# MicroController.net
KiCad netlist of a schematic drawn in Altium Designer
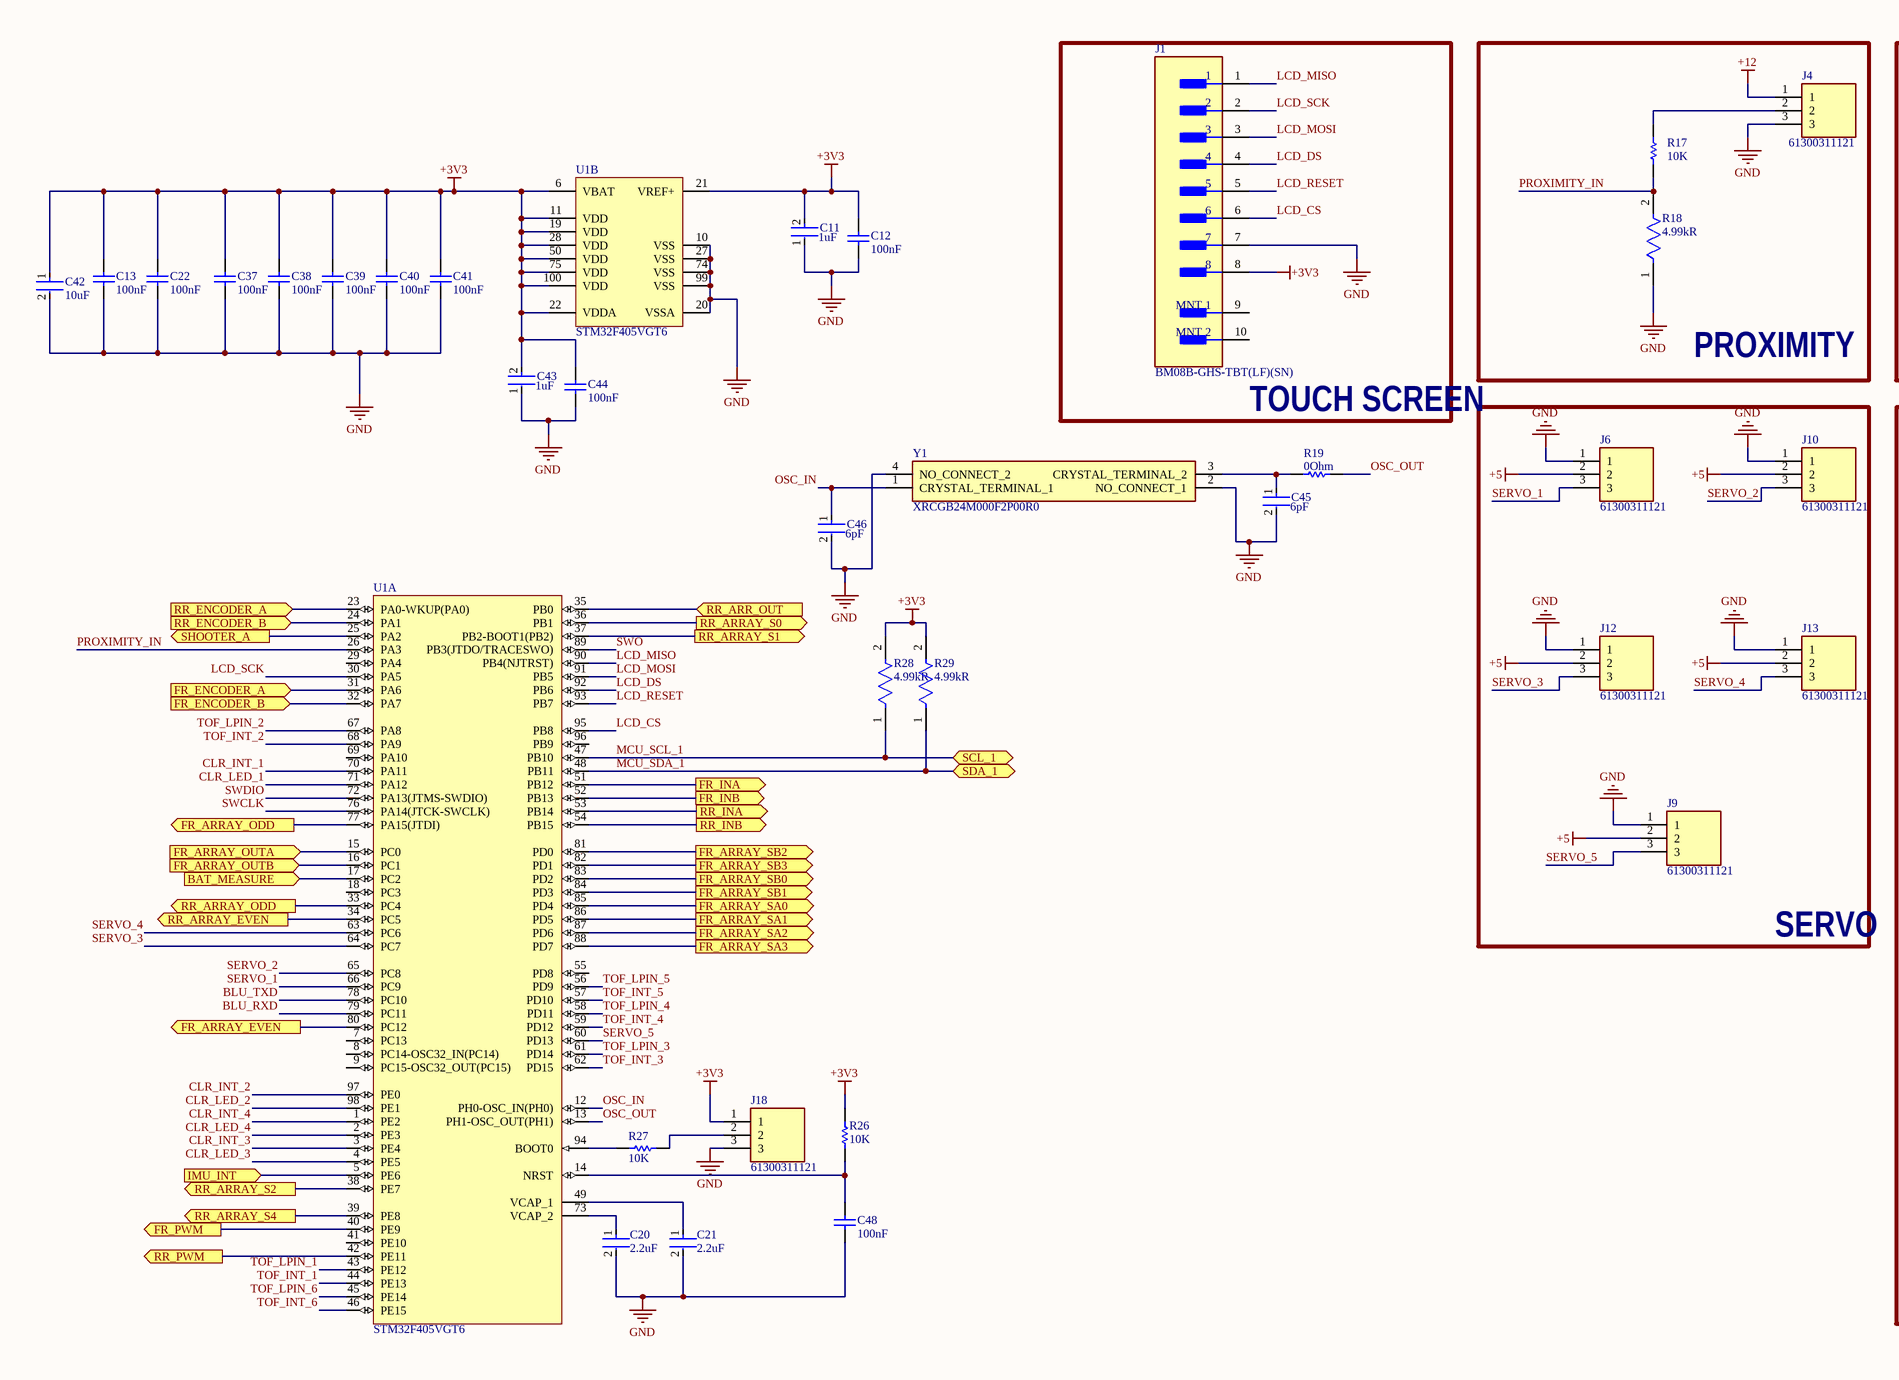
[diagram p0: MicroController.SchDoc, left]
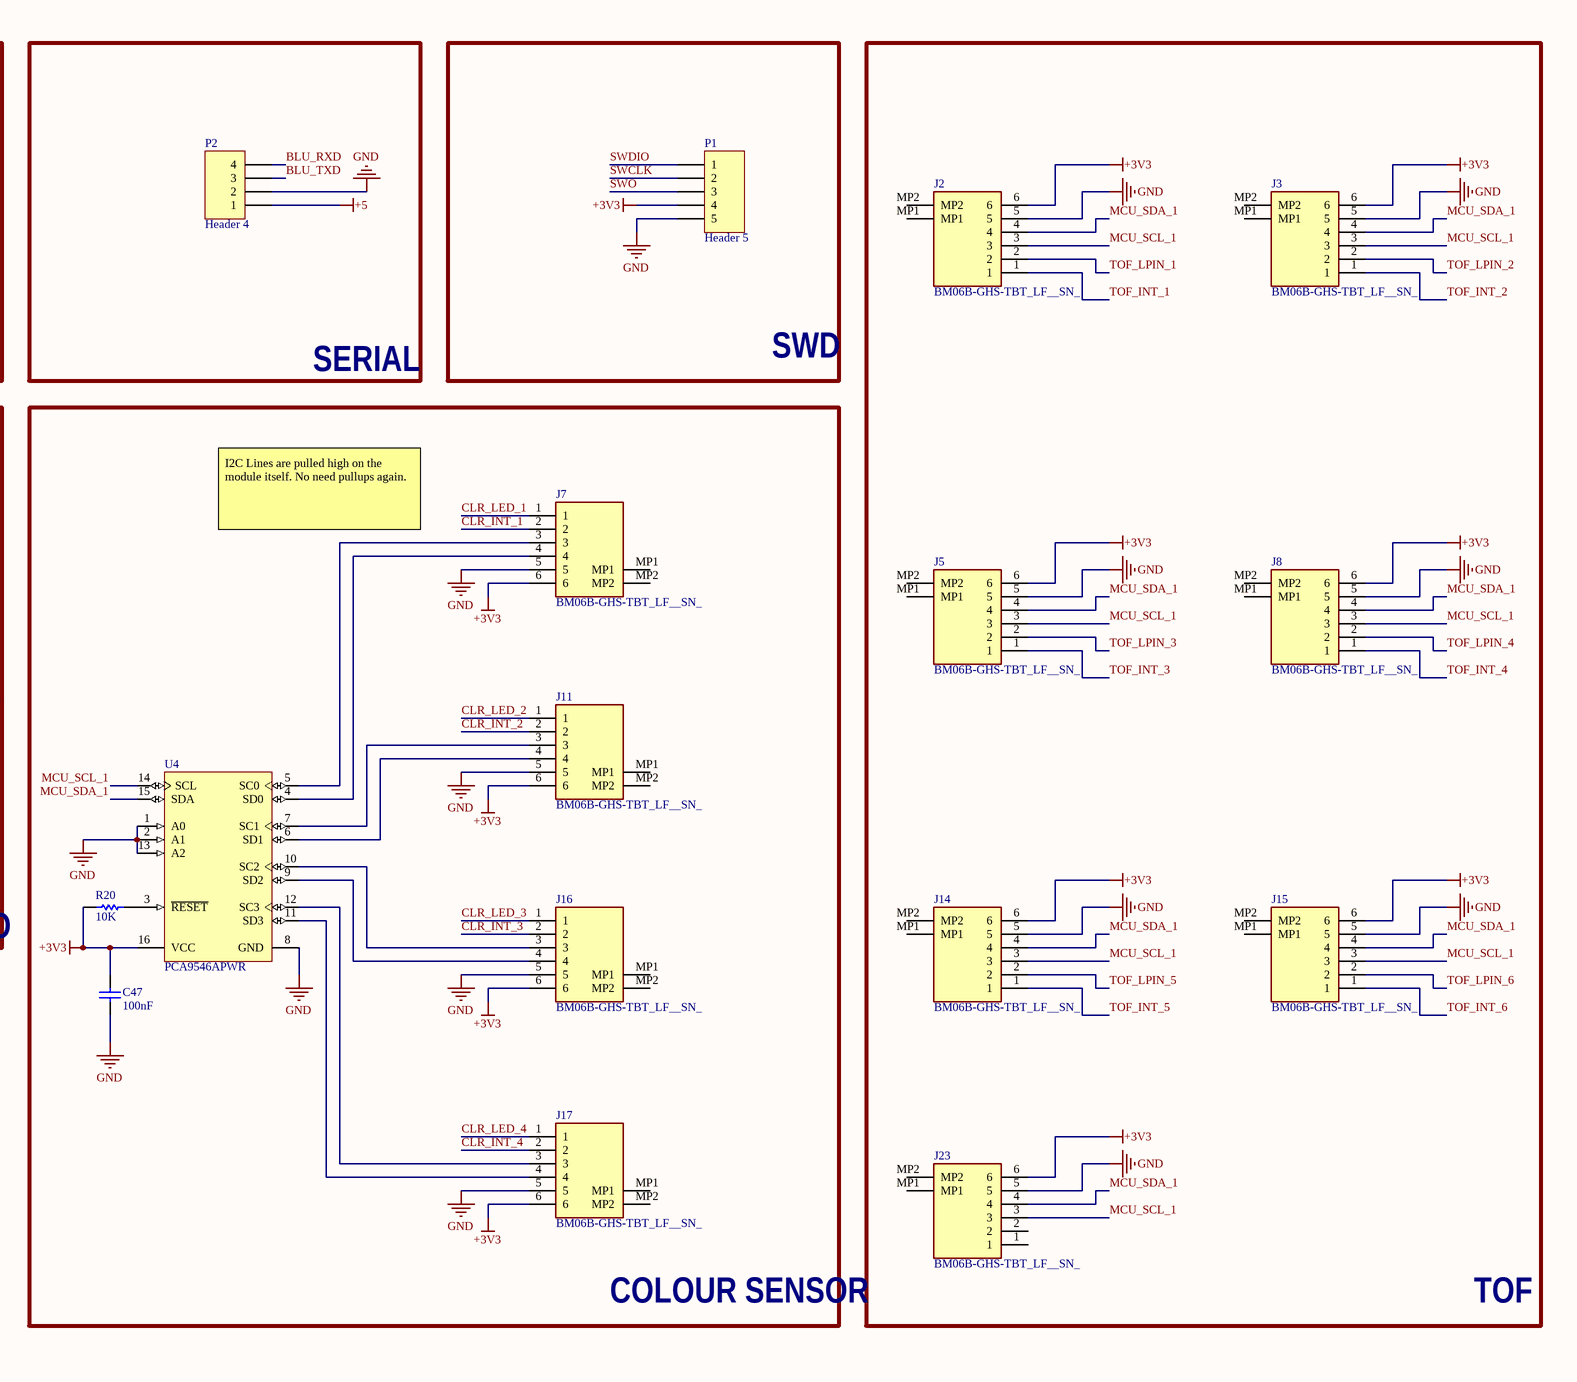
[diagram p1: MicroController.SchDoc, right]

(export (version "E")
  (design (tool "Eeschema 10.0.6"))
  (components
    (comp (ref "C11")
      (value "C1608X5R1H105K080AB")
      (footprint "FP-C1608-080-0_1-IPC_B")
      (description "Multilayer Ceramic Capacitors 1μF ±10% 50V X5R SMD 0603")
      (fields
        (field (name "VOLTAGE") "50V")
        (field (name "CAPACITANCE") "1uF")
        (field (name "TOLERANCE") "10%")
      )
      (libsource (lib "Altium Content Vault") (part "236180d848d6139a670b325ea6854c9"))
    )
    (comp (ref "C12")
      (value "CL05B104KO5NNNC")
      (footprint "CAPC1050X55X23ML05T13")
      (description "Chip Capacitor, 100 nF, +/- 10%, 16 V, -55 to 125 degC, 0402 (1005 Metric), RoHS, Tape and Reel")
      (fields (field (name "MANUFACTURER") "Samsung Electro-Mechanics") (field (name "CAPACITANCE") "100nF"))
      (libsource (lib "Altium Content Vault") (part "CAP-NP-2"))
    )
    (comp (ref "C13")
      (value "CL05B104KO5NNNC")
      (footprint "CAPC1050X55X23ML05T13")
      (description "Chip Capacitor, 100 nF, +/- 10%, 16 V, -55 to 125 degC, 0402 (1005 Metric), RoHS, Tape and Reel")
      (fields (field (name "MANUFACTURER") "Samsung Electro-Mechanics") (field (name "CAPACITANCE") "100nF"))
      (libsource (lib "Altium Content Vault") (part "CAP-NP-2"))
    )
    (comp (ref "C20")
      (value "GRM155R61A225KE95D")
      (footprint "FP-GRM155-0_05-MFG")
      (description "CAP CER 2.2UF 10V X5R 0402")
      (fields (field (name "CAPACITANCE") "2.2uF") (field (name "TOLERANCE") "10%"))
      (libsource (lib "Altium Content Vault") (part "b4654b650e69147ec39a6b967a45e02"))
    )
    (comp (ref "C21")
      (value "GRM155R61A225KE95D")
      (footprint "FP-GRM155-0_05-MFG")
      (description "CAP CER 2.2UF 10V X5R 0402")
      (fields (field (name "CAPACITANCE") "2.2uF") (field (name "TOLERANCE") "10%"))
      (libsource (lib "Altium Content Vault") (part "b4654b650e69147ec39a6b967a45e02"))
    )
    (comp (ref "C22")
      (value "CL05B104KO5NNNC")
      (footprint "CAPC1050X55X23ML05T13")
      (description "Chip Capacitor, 100 nF, +/- 10%, 16 V, -55 to 125 degC, 0402 (1005 Metric), RoHS, Tape and Reel")
      (fields (field (name "MANUFACTURER") "Samsung Electro-Mechanics") (field (name "CAPACITANCE") "100nF"))
      (libsource (lib "Altium Content Vault") (part "CAP-NP-2"))
    )
    (comp (ref "C37")
      (value "CL05B104KO5NNNC")
      (footprint "CAPC1050X55X23ML05T13")
      (description "Chip Capacitor, 100 nF, +/- 10%, 16 V, -55 to 125 degC, 0402 (1005 Metric), RoHS, Tape and Reel")
      (fields (field (name "MANUFACTURER") "Samsung Electro-Mechanics") (field (name "CAPACITANCE") "100nF"))
      (libsource (lib "Altium Content Vault") (part "CAP-NP-2"))
    )
    (comp (ref "C38")
      (value "CL05B104KO5NNNC")
      (footprint "CAPC1050X55X23ML05T13")
      (description "Chip Capacitor, 100 nF, +/- 10%, 16 V, -55 to 125 degC, 0402 (1005 Metric), RoHS, Tape and Reel")
      (fields (field (name "MANUFACTURER") "Samsung Electro-Mechanics") (field (name "CAPACITANCE") "100nF"))
      (libsource (lib "Altium Content Vault") (part "CAP-NP-2"))
    )
    (comp (ref "C39")
      (value "CL05B104KO5NNNC")
      (footprint "CAPC1050X55X23ML05T13")
      (description "Chip Capacitor, 100 nF, +/- 10%, 16 V, -55 to 125 degC, 0402 (1005 Metric), RoHS, Tape and Reel")
      (fields (field (name "MANUFACTURER") "Samsung Electro-Mechanics") (field (name "CAPACITANCE") "100nF"))
      (libsource (lib "Altium Content Vault") (part "CAP-NP-2"))
    )
    (comp (ref "C40")
      (value "CL05B104KO5NNNC")
      (footprint "CAPC1050X55X23ML05T13")
      (description "Chip Capacitor, 100 nF, +/- 10%, 16 V, -55 to 125 degC, 0402 (1005 Metric), RoHS, Tape and Reel")
      (fields (field (name "MANUFACTURER") "Samsung Electro-Mechanics") (field (name "CAPACITANCE") "100nF"))
      (libsource (lib "Altium Content Vault") (part "CAP-NP-2"))
    )
    (comp (ref "C41")
      (value "CL05B104KO5NNNC")
      (footprint "CAPC1050X55X23ML05T13")
      (description "Chip Capacitor, 100 nF, +/- 10%, 16 V, -55 to 125 degC, 0402 (1005 Metric), RoHS, Tape and Reel")
      (fields (field (name "MANUFACTURER") "Samsung Electro-Mechanics") (field (name "CAPACITANCE") "100nF"))
      (libsource (lib "Altium Content Vault") (part "CAP-NP-2"))
    )
    (comp (ref "C42")
      (value "CL05A106MP5NUNC")
      (footprint "FP-CL05A106MP5NUNC-MFG")
      (description "CAP CER 10UF 10V X5R 0402")
      (fields
        (field (name "OCTOPART") "https://octopart.com/cl05a106mp5nunc-samsung-22457395")
        (field (name "TOLERANCE") "20%")
        (field (name "CAPACITANCE") "10uF")
      )
      (libsource (lib "Altium Content Vault") (part "b4654b650e69147ec39a6b967a45e02"))
    )
    (comp (ref "C43")
      (value "C1608X5R1H105K080AB")
      (footprint "FP-C1608-080-0_1-IPC_B")
      (description "Multilayer Ceramic Capacitors 1μF ±10% 50V X5R SMD 0603")
      (fields
        (field (name "VOLTAGE") "50V")
        (field (name "CAPACITANCE") "1uF")
        (field (name "TOLERANCE") "10%")
      )
      (libsource (lib "Altium Content Vault") (part "236180d848d6139a670b325ea6854c9"))
    )
    (comp (ref "C44")
      (value "CL05B104KO5NNNC")
      (footprint "CAPC1050X55X23ML05T13")
      (description "Chip Capacitor, 100 nF, +/- 10%, 16 V, -55 to 125 degC, 0402 (1005 Metric), RoHS, Tape and Reel")
      (fields (field (name "MANUFACTURER") "Samsung Electro-Mechanics") (field (name "CAPACITANCE") "100nF"))
      (libsource (lib "Altium Content Vault") (part "CAP-NP-2"))
    )
    (comp (ref "C45")
      (value "6pF")
      (footprint "FP-GRT155-0_05-MFG")
      (description "Multi-Layer Ceramic Capacitor 6pF 50V C0G ±0.5pF 0402 Paper T/R")
      (fields (field (name "Comment") "GRT1555C1H6R0DA02D"))
      (libsource (lib "Altium Content Vault") (part "02cd4be3c70576c341d710602a673aa"))
    )
    (comp (ref "C46")
      (value "6pF")
      (footprint "FP-GRT155-0_05-MFG")
      (description "Multi-Layer Ceramic Capacitor 6pF 50V C0G ±0.5pF 0402 Paper T/R")
      (fields (field (name "Comment") "GRT1555C1H6R0DA02D"))
      (libsource (lib "Altium Content Vault") (part "02cd4be3c70576c341d710602a673aa"))
    )
    (comp (ref "C47")
      (value "CL05B104KO5NNNC")
      (footprint "CAPC1050X55X23ML05T13")
      (description "Chip Capacitor, 100 nF, +/- 10%, 16 V, -55 to 125 degC, 0402 (1005 Metric), RoHS, Tape and Reel")
      (fields (field (name "MANUFACTURER") "Samsung Electro-Mechanics") (field (name "CAPACITANCE") "100nF"))
      (libsource (lib "Altium Content Vault") (part "CAP-NP-2"))
    )
    (comp (ref "C48")
      (value "CL05B104KO5NNNC")
      (footprint "CAPC1050X55X23ML05T13")
      (description "Chip Capacitor, 100 nF, +/- 10%, 16 V, -55 to 125 degC, 0402 (1005 Metric), RoHS, Tape and Reel")
      (fields (field (name "MANUFACTURER") "Samsung Electro-Mechanics") (field (name "CAPACITANCE") "100nF"))
      (libsource (lib "Altium Content Vault") (part "CAP-NP-2"))
    )
    (comp (ref "J1")
      (value "BM08B-GHS-TBT(LF)(SN)")
      (footprint "FP-BM08B-GHS-TBT_LF_SN-MFG")
      (description "CONN HEADER SMD 8POS 1.25MM")
      (libsource (lib "Altium Content Vault") (part "98b5586d6b3804e276fbd0410cd4945"))
    )
    (comp (ref "J2")
      (value "BM06B-GHS-TBT_LF__SN_")
      (footprint "SamacSys:BM06BGHSTBTLFSN")
      (description "Connector")
      (fields (field (name "MANUFACTURER_PART_NUMBER") "BM06B-GHS-TBT(LF)(SN)"))
      (libsource (lib "") (part "BM06B-GHS-TBT_LF__SN__1"))
    )
    (comp (ref "J3")
      (value "BM06B-GHS-TBT_LF__SN_")
      (footprint "SamacSys:BM06BGHSTBTLFSN")
      (description "Connector")
      (fields (field (name "MANUFACTURER_PART_NUMBER") "BM06B-GHS-TBT(LF)(SN)"))
      (libsource (lib "") (part "BM06B-GHS-TBT_LF__SN__1"))
    )
    (comp (ref "J4")
      (value "61300311121")
      (footprint "SamacSys:HDRV3W64P0X254_1X3_762X254X869P")
      (description "Connector")
      (fields (field (name "MOUSER PART NUMBER") "710-61300311121"))
      (libsource (lib "SamacSys") (part "61300311121"))
    )
    (comp (ref "J5")
      (value "BM06B-GHS-TBT_LF__SN_")
      (footprint "SamacSys:BM06BGHSTBTLFSN")
      (description "Connector")
      (fields (field (name "MANUFACTURER_PART_NUMBER") "BM06B-GHS-TBT(LF)(SN)"))
      (libsource (lib "") (part "BM06B-GHS-TBT_LF__SN__1"))
    )
    (comp (ref "J6")
      (value "61300311121")
      (footprint "SamacSys:HDRV3W64P0X254_1X3_762X254X869P")
      (description "Connector")
      (fields (field (name "MOUSER PART NUMBER") "710-61300311121"))
      (libsource (lib "SamacSys") (part "61300311121"))
    )
    (comp (ref "J7")
      (value "BM06B-GHS-TBT_LF__SN_")
      (footprint "SamacSys:BM06BGHSTBTLFSN")
      (description "Connector")
      (fields (field (name "MANUFACTURER_PART_NUMBER") "BM06B-GHS-TBT(LF)(SN)"))
      (libsource (lib "SamacSys") (part "BM06B-GHS-TBT_LF__SN_"))
    )
    (comp (ref "J8")
      (value "BM06B-GHS-TBT_LF__SN_")
      (footprint "SamacSys:BM06BGHSTBTLFSN")
      (description "Connector")
      (fields (field (name "MANUFACTURER_PART_NUMBER") "BM06B-GHS-TBT(LF)(SN)"))
      (libsource (lib "") (part "BM06B-GHS-TBT_LF__SN__1"))
    )
    (comp (ref "J9")
      (value "61300311121")
      (footprint "SamacSys:HDRV3W64P0X254_1X3_762X254X869P")
      (description "Connector")
      (fields (field (name "MOUSER PART NUMBER") "710-61300311121"))
      (libsource (lib "SamacSys") (part "61300311121"))
    )
    (comp (ref "J10")
      (value "61300311121")
      (footprint "SamacSys:HDRV3W64P0X254_1X3_762X254X869P")
      (description "Connector")
      (fields (field (name "MOUSER PART NUMBER") "710-61300311121"))
      (libsource (lib "SamacSys") (part "61300311121"))
    )
    (comp (ref "J11")
      (value "BM06B-GHS-TBT_LF__SN_")
      (footprint "SamacSys:BM06BGHSTBTLFSN")
      (description "Connector")
      (fields (field (name "MANUFACTURER_PART_NUMBER") "BM06B-GHS-TBT(LF)(SN)"))
      (libsource (lib "SamacSys") (part "BM06B-GHS-TBT_LF__SN_"))
    )
    (comp (ref "J12")
      (value "61300311121")
      (footprint "SamacSys:HDRV3W64P0X254_1X3_762X254X869P")
      (description "Connector")
      (fields (field (name "MOUSER PART NUMBER") "710-61300311121"))
      (libsource (lib "SamacSys") (part "61300311121"))
    )
    (comp (ref "J13")
      (value "61300311121")
      (footprint "SamacSys:HDRV3W64P0X254_1X3_762X254X869P")
      (description "Connector")
      (fields (field (name "MOUSER PART NUMBER") "710-61300311121"))
      (libsource (lib "SamacSys") (part "61300311121"))
    )
    (comp (ref "J14")
      (value "BM06B-GHS-TBT_LF__SN_")
      (footprint "SamacSys:BM06BGHSTBTLFSN")
      (description "Connector")
      (fields (field (name "MANUFACTURER_PART_NUMBER") "BM06B-GHS-TBT(LF)(SN)"))
      (libsource (lib "") (part "BM06B-GHS-TBT_LF__SN__1"))
    )
    (comp (ref "J15")
      (value "BM06B-GHS-TBT_LF__SN_")
      (footprint "SamacSys:BM06BGHSTBTLFSN")
      (description "Connector")
      (fields (field (name "MANUFACTURER_PART_NUMBER") "BM06B-GHS-TBT(LF)(SN)"))
      (libsource (lib "") (part "BM06B-GHS-TBT_LF__SN__1"))
    )
    (comp (ref "J16")
      (value "BM06B-GHS-TBT_LF__SN_")
      (footprint "SamacSys:BM06BGHSTBTLFSN")
      (description "Connector")
      (fields (field (name "MANUFACTURER_PART_NUMBER") "BM06B-GHS-TBT(LF)(SN)"))
      (libsource (lib "SamacSys") (part "BM06B-GHS-TBT_LF__SN_"))
    )
    (comp (ref "J17")
      (value "BM06B-GHS-TBT_LF__SN_")
      (footprint "SamacSys:BM06BGHSTBTLFSN")
      (description "Connector")
      (fields (field (name "MANUFACTURER_PART_NUMBER") "BM06B-GHS-TBT(LF)(SN)"))
      (libsource (lib "SamacSys") (part "BM06B-GHS-TBT_LF__SN_"))
    )
    (comp (ref "J18")
      (value "61300311121")
      (footprint "SamacSys:HDRV3W64P0X254_1X3_762X254X869P")
      (description "Connector")
      (fields (field (name "MOUSER PART NUMBER") "710-61300311121"))
      (libsource (lib "SamacSys") (part "61300311121"))
    )
    (comp (ref "J23")
      (value "BM06B-GHS-TBT_LF__SN_")
      (footprint "SamacSys:BM06BGHSTBTLFSN")
      (description "Connector")
      (fields (field (name "MANUFACTURER_PART_NUMBER") "BM06B-GHS-TBT(LF)(SN)"))
      (libsource (lib "") (part "BM06B-GHS-TBT_LF__SN__1"))
    )
    (comp (ref "P1")
      (value "Header 5")
      (footprint "HDR1X5")
      (description "Header, 5-Pin")
      (fields (field (name "PUBLISHER") "Altium Limited"))
      (libsource (lib "Miscellaneous Connectors") (part "Header 5"))
    )
    (comp (ref "P2")
      (value "Header 4")
      (footprint "HDR1X4")
      (description "Header, 4-Pin")
      (fields (field (name "PUBLISHER") "Altium Limited"))
      (libsource (lib "Miscellaneous Connectors") (part "Header 4"))
    )
    (comp (ref "R17")
      (value "RC0402FR-0710KL")
      (footprint "RESC1005X40X25LL05T10")
      (fields (field (name "MANUFACTURER") "Yageo / Phycomp") (field (name "RESISTANCE") "10K"))
      (libsource (lib "Altium Content Vault") (part "RES"))
    )
    (comp (ref "R18")
      (value "CRCW04024K99FKED")
      (footprint "FP-CRCW0402-e3-MFG")
      (description "RES Thick Film, 4.99kΩ, 1%, 0.063W, 100ppm/°C, 0402")
      (fields (field (name "RESISTANCE") "4.99kR") (field (name "TOLERANCE") "1%"))
      (libsource (lib "Altium Content Vault") (part "1029c3af85768c4190bb7ad29bc67b5"))
    )
    (comp (ref "R19")
      (value "0Ohm")
      (footprint "RESC1005X40X25NL05T10")
      (fields (field (name "MANUFACTURER") "Yageo / Phycomp") (field (name "PART NUMBER") "RC0402JR-070RL"))
      (libsource (lib "Altium Content Vault") (part "RES"))
    )
    (comp (ref "R20")
      (value "RC0402FR-0710KL")
      (footprint "RESC1005X40X25LL05T10")
      (fields (field (name "MANUFACTURER") "Yageo / Phycomp") (field (name "RESISTANCE") "10K"))
      (libsource (lib "Altium Content Vault") (part "RES"))
    )
    (comp (ref "R26")
      (value "RC0402FR-0710KL")
      (footprint "RESC1005X40X25LL05T10")
      (fields (field (name "MANUFACTURER") "Yageo / Phycomp") (field (name "RESISTANCE") "10K"))
      (libsource (lib "Altium Content Vault") (part "RES"))
    )
    (comp (ref "R27")
      (value "RC0402FR-0710KL")
      (footprint "RESC1005X40X25LL05T10")
      (fields (field (name "MANUFACTURER") "Yageo / Phycomp") (field (name "RESISTANCE") "10K"))
      (libsource (lib "Altium Content Vault") (part "RES"))
    )
    (comp (ref "R28")
      (value "CRCW04024K99FKED")
      (footprint "FP-CRCW0402-e3-MFG")
      (description "RES Thick Film, 4.99kΩ, 1%, 0.063W, 100ppm/°C, 0402")
      (fields (field (name "RESISTANCE") "4.99kR") (field (name "TOLERANCE") "1%"))
      (libsource (lib "Altium Content Vault") (part "1029c3af85768c4190bb7ad29bc67b5"))
    )
    (comp (ref "R29")
      (value "CRCW04024K99FKED")
      (footprint "FP-CRCW0402-e3-MFG")
      (description "RES Thick Film, 4.99kΩ, 1%, 0.063W, 100ppm/°C, 0402")
      (fields (field (name "RESISTANCE") "4.99kR") (field (name "TOLERANCE") "1%"))
      (libsource (lib "Altium Content Vault") (part "1029c3af85768c4190bb7ad29bc67b5"))
    )
    (comp (ref "U1")
      (value "STM32F405VGT6")
      (footprint "STM-LQFP100_V")
      (fields (field (name "MANUFACTURER") "STMicroelectronics"))
      (libsource (lib "Altium Content Vault") (part "MC-ARM-STM32F40X_41X-SQ100"))
    )
    (comp (ref "U4")
      (value "PCA9546APWR")
      (footprint "PW0016A_N")
      (fields (field (name "MANUFACTURER") "Texas Instruments"))
      (libsource (lib "Altium Content Vault") (part "TI-PCA9546A-TSSOP_PW-16"))
    )
    (comp (ref "Y1")
      (value "XRCGB24M000F2P00R0")
      (footprint "SamacSys:XRCGB24M000F2P00R0")
      (description "Crystal or Oscillator")
      (fields (field (name "MOUSER PART NUMBER") "81-XRCGB24M000F2P0R0"))
      (libsource (lib "*") (part "XRCGB24M000F2P00R0"))
    )
  )
  (nets
    (net (code "1") (name "+3V3") (class "Default")
      (node (ref "C11") (pin "2") (pinfunction "2_2") (pintype "passive"))
      (node (ref "C12") (pin "1") (pinfunction "1_1") (pintype "passive"))
      (node (ref "C13") (pin "1") (pinfunction "1_1") (pintype "passive"))
      (node (ref "C22") (pin "1") (pinfunction "1_1") (pintype "passive"))
      (node (ref "C37") (pin "1") (pinfunction "1_1") (pintype "passive"))
      (node (ref "C38") (pin "1") (pinfunction "1_1") (pintype "passive"))
      (node (ref "C39") (pin "1") (pinfunction "1_1") (pintype "passive"))
      (node (ref "C40") (pin "1") (pinfunction "1_1") (pintype "passive"))
      (node (ref "C41") (pin "1") (pinfunction "1_1") (pintype "passive"))
      (node (ref "C42") (pin "1") (pinfunction "1_1") (pintype "passive"))
      (node (ref "C43") (pin "2") (pinfunction "2_2") (pintype "passive"))
      (node (ref "C44") (pin "1") (pinfunction "1_1") (pintype "passive"))
      (node (ref "C47") (pin "1") (pinfunction "1_1") (pintype "passive"))
      (node (ref "J1") (pin "8") (pinfunction "8_8") (pintype "passive"))
      (node (ref "J11") (pin "6") (pinfunction "6_6") (pintype "passive"))
      (node (ref "J14") (pin "6") (pinfunction "6_6") (pintype "passive"))
      (node (ref "J15") (pin "6") (pinfunction "6_6") (pintype "passive"))
      (node (ref "J16") (pin "6") (pinfunction "6_6") (pintype "passive"))
      (node (ref "J17") (pin "6") (pinfunction "6_6") (pintype "passive"))
      (node (ref "J18") (pin "1") (pinfunction "1_1") (pintype "passive"))
      (node (ref "J2") (pin "6") (pinfunction "6_6") (pintype "passive"))
      (node (ref "J23") (pin "6") (pinfunction "6_6") (pintype "passive"))
      (node (ref "J3") (pin "6") (pinfunction "6_6") (pintype "passive"))
      (node (ref "J5") (pin "6") (pinfunction "6_6") (pintype "passive"))
      (node (ref "J7") (pin "6") (pinfunction "6_6") (pintype "passive"))
      (node (ref "J8") (pin "6") (pinfunction "6_6") (pintype "passive"))
      (node (ref "P1") (pin "4") (pinfunction "4_4") (pintype "passive"))
      (node (ref "R20") (pin "2") (pinfunction "2_2") (pintype "passive"))
      (node (ref "R26") (pin "1") (pinfunction "1_1") (pintype "passive"))
      (node (ref "R28") (pin "2") (pinfunction "2_2") (pintype "passive"))
      (node (ref "R29") (pin "2") (pinfunction "2_2") (pintype "passive"))
      (node (ref "U1") (pin "100") (pinfunction "VDD_100") (pintype "power_in"))
      (node (ref "U1") (pin "11") (pinfunction "VDD_11") (pintype "power_in"))
      (node (ref "U1") (pin "19") (pinfunction "VDD_19") (pintype "power_in"))
      (node (ref "U1") (pin "21") (pinfunction "VREF+_21") (pintype "power_in"))
      (node (ref "U1") (pin "22") (pinfunction "VDDA_22") (pintype "power_in"))
      (node (ref "U1") (pin "28") (pinfunction "VDD_28") (pintype "power_in"))
      (node (ref "U1") (pin "50") (pinfunction "VDD_50") (pintype "power_in"))
      (node (ref "U1") (pin "6") (pinfunction "VBAT_6") (pintype "power_in"))
      (node (ref "U1") (pin "75") (pinfunction "VDD_75") (pintype "power_in"))
      (node (ref "U4") (pin "16") (pinfunction "VCC_16") (pintype "power_in"))
    )
    (net (code "2") (name "+5") (class "Default")
      (node (ref "J10") (pin "2") (pinfunction "2_2") (pintype "passive"))
      (node (ref "J12") (pin "2") (pinfunction "2_2") (pintype "passive"))
      (node (ref "J13") (pin "2") (pinfunction "2_2") (pintype "passive"))
      (node (ref "J6") (pin "2") (pinfunction "2_2") (pintype "passive"))
      (node (ref "J9") (pin "2") (pinfunction "2_2") (pintype "passive"))
      (node (ref "P2") (pin "1") (pinfunction "1_1") (pintype "passive"))
    )
    (net (code "3") (name "+12") (class "Default")
      (node (ref "J4") (pin "1") (pinfunction "1_1") (pintype "passive"))
    )
    (net (code "4") (name "/BAT_MEASURE") (class "Default")
      (node (ref "U1") (pin "17") (pinfunction "PC2_17") (pintype "bidirectional"))
    )
    (net (code "5") (name "/BLU_RXD") (class "Default")
      (node (ref "P2") (pin "4") (pinfunction "4_4") (pintype "passive"))
      (node (ref "U1") (pin "79") (pinfunction "PC11_79") (pintype "bidirectional"))
    )
    (net (code "6") (name "/BLU_TXD") (class "Default")
      (node (ref "P2") (pin "3") (pinfunction "3_3") (pintype "passive"))
      (node (ref "U1") (pin "78") (pinfunction "PC10_78") (pintype "bidirectional"))
    )
    (net (code "7") (name "/CLR_INT_1") (class "Default")
      (node (ref "J7") (pin "2") (pinfunction "2_2") (pintype "passive"))
      (node (ref "U1") (pin "70") (pinfunction "PA11_70") (pintype "bidirectional"))
    )
    (net (code "8") (name "/CLR_INT_2") (class "Default")
      (node (ref "J11") (pin "2") (pinfunction "2_2") (pintype "passive"))
      (node (ref "U1") (pin "97") (pinfunction "PE0_97") (pintype "bidirectional"))
    )
    (net (code "9") (name "/CLR_INT_3") (class "Default")
      (node (ref "J16") (pin "2") (pinfunction "2_2") (pintype "passive"))
      (node (ref "U1") (pin "3") (pinfunction "PE4_3") (pintype "bidirectional"))
    )
    (net (code "10") (name "/CLR_INT_4") (class "Default")
      (node (ref "J17") (pin "2") (pinfunction "2_2") (pintype "passive"))
      (node (ref "U1") (pin "1") (pinfunction "PE2_1") (pintype "bidirectional"))
    )
    (net (code "11") (name "/CLR_LED_1") (class "Default")
      (node (ref "J7") (pin "1") (pinfunction "1_1") (pintype "passive"))
      (node (ref "U1") (pin "71") (pinfunction "PA12_71") (pintype "bidirectional"))
    )
    (net (code "12") (name "/CLR_LED_2") (class "Default")
      (node (ref "J11") (pin "1") (pinfunction "1_1") (pintype "passive"))
      (node (ref "U1") (pin "98") (pinfunction "PE1_98") (pintype "bidirectional"))
    )
    (net (code "13") (name "/CLR_LED_3") (class "Default")
      (node (ref "J16") (pin "1") (pinfunction "1_1") (pintype "passive"))
      (node (ref "U1") (pin "4") (pinfunction "PE5_4") (pintype "bidirectional"))
    )
    (net (code "14") (name "/CLR_LED_4") (class "Default")
      (node (ref "J17") (pin "1") (pinfunction "1_1") (pintype "passive"))
      (node (ref "U1") (pin "2") (pinfunction "PE3_2") (pintype "bidirectional"))
    )
    (net (code "15") (name "/FR_ARRAY_EVEN") (class "Default")
      (node (ref "U1") (pin "80") (pinfunction "PC12_80") (pintype "bidirectional"))
    )
    (net (code "16") (name "/FR_ARRAY_ODD") (class "Default")
      (node (ref "U1") (pin "77") (pinfunction "PA15(JTDI)_77") (pintype "bidirectional"))
    )
    (net (code "17") (name "/FR_ARRAY_OUTA") (class "Default")
      (node (ref "U1") (pin "15") (pinfunction "PC0_15") (pintype "bidirectional"))
    )
    (net (code "18") (name "/FR_ARRAY_OUTB") (class "Default")
      (node (ref "U1") (pin "16") (pinfunction "PC1_16") (pintype "bidirectional"))
    )
    (net (code "19") (name "/FR_ARRAY_SA0") (class "Default")
      (node (ref "U1") (pin "85") (pinfunction "PD4_85") (pintype "bidirectional"))
    )
    (net (code "20") (name "/FR_ARRAY_SA1") (class "Default")
      (node (ref "U1") (pin "86") (pinfunction "PD5_86") (pintype "bidirectional"))
    )
    (net (code "21") (name "/FR_ARRAY_SA2") (class "Default")
      (node (ref "U1") (pin "87") (pinfunction "PD6_87") (pintype "bidirectional"))
    )
    (net (code "22") (name "/FR_ARRAY_SA3") (class "Default")
      (node (ref "U1") (pin "88") (pinfunction "PD7_88") (pintype "bidirectional"))
    )
    (net (code "23") (name "/FR_ARRAY_SB0") (class "Default")
      (node (ref "U1") (pin "83") (pinfunction "PD2_83") (pintype "bidirectional"))
    )
    (net (code "24") (name "/FR_ARRAY_SB1") (class "Default")
      (node (ref "U1") (pin "84") (pinfunction "PD3_84") (pintype "bidirectional"))
    )
    (net (code "25") (name "/FR_ARRAY_SB2") (class "Default")
      (node (ref "U1") (pin "81") (pinfunction "PD0_81") (pintype "bidirectional"))
    )
    (net (code "26") (name "/FR_ARRAY_SB3") (class "Default")
      (node (ref "U1") (pin "82") (pinfunction "PD1_82") (pintype "bidirectional"))
    )
    (net (code "27") (name "/FR_ENCODER_A") (class "Default")
      (node (ref "U1") (pin "31") (pinfunction "PA6_31") (pintype "bidirectional"))
    )
    (net (code "28") (name "/FR_ENCODER_B") (class "Default")
      (node (ref "U1") (pin "32") (pinfunction "PA7_32") (pintype "bidirectional"))
    )
    (net (code "29") (name "/FR_INA") (class "Default")
      (node (ref "U1") (pin "51") (pinfunction "PB12_51") (pintype "bidirectional"))
    )
    (net (code "30") (name "/FR_INB") (class "Default")
      (node (ref "U1") (pin "52") (pinfunction "PB13_52") (pintype "bidirectional"))
    )
    (net (code "31") (name "/FR_PWM") (class "Default")
      (node (ref "U1") (pin "40") (pinfunction "PE9_40") (pintype "bidirectional"))
    )
    (net (code "32") (name "/IMU_INT") (class "Default")
      (node (ref "U1") (pin "5") (pinfunction "PE6_5") (pintype "bidirectional"))
    )
    (net (code "33") (name "/LCD_CS") (class "Default")
      (node (ref "J1") (pin "6") (pinfunction "6_6") (pintype "passive"))
      (node (ref "U1") (pin "95") (pinfunction "PB8_95") (pintype "bidirectional"))
    )
    (net (code "34") (name "/LCD_DS") (class "Default")
      (node (ref "J1") (pin "4") (pinfunction "4_4") (pintype "passive"))
      (node (ref "U1") (pin "92") (pinfunction "PB6_92") (pintype "bidirectional"))
    )
    (net (code "35") (name "/LCD_MISO") (class "Default")
      (node (ref "J1") (pin "1") (pinfunction "1_1") (pintype "passive"))
      (node (ref "U1") (pin "90") (pinfunction "PB4(NJTRST)_90") (pintype "bidirectional"))
    )
    (net (code "36") (name "/LCD_MOSI") (class "Default")
      (node (ref "J1") (pin "3") (pinfunction "3_3") (pintype "passive"))
      (node (ref "U1") (pin "91") (pinfunction "PB5_91") (pintype "bidirectional"))
    )
    (net (code "37") (name "/LCD_RESET") (class "Default")
      (node (ref "J1") (pin "5") (pinfunction "5_5") (pintype "passive"))
      (node (ref "U1") (pin "93") (pinfunction "PB7_93") (pintype "bidirectional"))
    )
    (net (code "38") (name "/LCD_SCK") (class "Default")
      (node (ref "J1") (pin "2") (pinfunction "2_2") (pintype "passive"))
      (node (ref "U1") (pin "30") (pinfunction "PA5_30") (pintype "bidirectional"))
    )
    (net (code "39") (name "/MCU_SCL_1") (class "Default")
      (node (ref "J14") (pin "3") (pinfunction "3_3") (pintype "passive"))
      (node (ref "J15") (pin "3") (pinfunction "3_3") (pintype "passive"))
      (node (ref "J2") (pin "3") (pinfunction "3_3") (pintype "passive"))
      (node (ref "J23") (pin "3") (pinfunction "3_3") (pintype "passive"))
      (node (ref "J3") (pin "3") (pinfunction "3_3") (pintype "passive"))
      (node (ref "J5") (pin "3") (pinfunction "3_3") (pintype "passive"))
      (node (ref "J8") (pin "3") (pinfunction "3_3") (pintype "passive"))
      (node (ref "R28") (pin "1") (pinfunction "1_1") (pintype "passive"))
      (node (ref "U1") (pin "47") (pinfunction "PB10_47") (pintype "bidirectional"))
      (node (ref "U4") (pin "14") (pinfunction "SCL_14") (pintype "bidirectional"))
    )
    (net (code "40") (name "/MCU_SDA_1") (class "Default")
      (node (ref "J14") (pin "4") (pinfunction "4_4") (pintype "passive"))
      (node (ref "J15") (pin "4") (pinfunction "4_4") (pintype "passive"))
      (node (ref "J2") (pin "4") (pinfunction "4_4") (pintype "passive"))
      (node (ref "J23") (pin "4") (pinfunction "4_4") (pintype "passive"))
      (node (ref "J3") (pin "4") (pinfunction "4_4") (pintype "passive"))
      (node (ref "J5") (pin "4") (pinfunction "4_4") (pintype "passive"))
      (node (ref "J8") (pin "4") (pinfunction "4_4") (pintype "passive"))
      (node (ref "R29") (pin "1") (pinfunction "1_1") (pintype "passive"))
      (node (ref "U1") (pin "48") (pinfunction "PB11_48") (pintype "bidirectional"))
      (node (ref "U4") (pin "15") (pinfunction "SDA_15") (pintype "bidirectional"))
    )
    (net (code "41") (name "/OSC_IN") (class "Default")
      (node (ref "C46") (pin "1") (pinfunction "1_1") (pintype "passive"))
      (node (ref "U1") (pin "12") (pinfunction "PH0-OSC_IN(PH0)_12") (pintype "bidirectional"))
      (node (ref "Y1") (pin "1") (pinfunction "CRYSTAL_TERMINAL_1_1") (pintype "passive"))
    )
    (net (code "42") (name "/OSC_OUT") (class "Default")
      (node (ref "R19") (pin "2") (pinfunction "2_2") (pintype "passive"))
      (node (ref "U1") (pin "13") (pinfunction "PH1-OSC_OUT(PH1)_13") (pintype "bidirectional"))
    )
    (net (code "43") (name "/PROXIMITY_IN") (class "Default")
      (node (ref "R17") (pin "1") (pinfunction "1_1") (pintype "passive"))
      (node (ref "R18") (pin "2") (pinfunction "2_2") (pintype "passive"))
      (node (ref "U1") (pin "26") (pinfunction "PA3_26") (pintype "bidirectional"))
    )
    (net (code "44") (name "/RR_ARRAY_EVEN") (class "Default")
      (node (ref "U1") (pin "34") (pinfunction "PC5_34") (pintype "bidirectional"))
    )
    (net (code "45") (name "/RR_ARRAY_ODD") (class "Default")
      (node (ref "U1") (pin "33") (pinfunction "PC4_33") (pintype "bidirectional"))
    )
    (net (code "46") (name "/RR_ARRAY_S0") (class "Default")
      (node (ref "U1") (pin "36") (pinfunction "PB1_36") (pintype "bidirectional"))
    )
    (net (code "47") (name "/RR_ARRAY_S1") (class "Default")
      (node (ref "U1") (pin "37") (pinfunction "PB2-BOOT1(PB2)_37") (pintype "bidirectional"))
    )
    (net (code "48") (name "/RR_ARRAY_S2") (class "Default")
      (node (ref "U1") (pin "38") (pinfunction "PE7_38") (pintype "bidirectional"))
    )
    (net (code "49") (name "/RR_ARRAY_S4") (class "Default")
      (node (ref "U1") (pin "39") (pinfunction "PE8_39") (pintype "bidirectional"))
    )
    (net (code "50") (name "/RR_ARR_OUT") (class "Default")
      (node (ref "U1") (pin "35") (pinfunction "PB0_35") (pintype "bidirectional"))
    )
    (net (code "51") (name "/RR_ENCODER_A") (class "Default")
      (node (ref "U1") (pin "23") (pinfunction "PA0-WKUP(PA0)_23") (pintype "bidirectional"))
    )
    (net (code "52") (name "/RR_ENCODER_B") (class "Default")
      (node (ref "U1") (pin "24") (pinfunction "PA1_24") (pintype "bidirectional"))
    )
    (net (code "53") (name "/RR_INA") (class "Default")
      (node (ref "U1") (pin "53") (pinfunction "PB14_53") (pintype "bidirectional"))
    )
    (net (code "54") (name "/RR_INB") (class "Default")
      (node (ref "U1") (pin "54") (pinfunction "PB15_54") (pintype "bidirectional"))
    )
    (net (code "55") (name "/RR_PWM") (class "Default")
      (node (ref "U1") (pin "42") (pinfunction "PE11_42") (pintype "bidirectional"))
    )
    (net (code "56") (name "/SERVO_1") (class "Default")
      (node (ref "J6") (pin "3") (pinfunction "3_3") (pintype "passive"))
      (node (ref "U1") (pin "66") (pinfunction "PC9_66") (pintype "bidirectional"))
    )
    (net (code "57") (name "/SERVO_2") (class "Default")
      (node (ref "J10") (pin "3") (pinfunction "3_3") (pintype "passive"))
      (node (ref "U1") (pin "65") (pinfunction "PC8_65") (pintype "bidirectional"))
    )
    (net (code "58") (name "/SERVO_3") (class "Default")
      (node (ref "J12") (pin "3") (pinfunction "3_3") (pintype "passive"))
      (node (ref "U1") (pin "64") (pinfunction "PC7_64") (pintype "bidirectional"))
    )
    (net (code "59") (name "/SERVO_4") (class "Default")
      (node (ref "J13") (pin "3") (pinfunction "3_3") (pintype "passive"))
      (node (ref "U1") (pin "63") (pinfunction "PC6_63") (pintype "bidirectional"))
    )
    (net (code "60") (name "/SERVO_5") (class "Default")
      (node (ref "J9") (pin "3") (pinfunction "3_3") (pintype "passive"))
      (node (ref "U1") (pin "60") (pinfunction "PD13_60") (pintype "bidirectional"))
    )
    (net (code "61") (name "/SHOOTER_A") (class "Default")
      (node (ref "U1") (pin "25") (pinfunction "PA2_25") (pintype "bidirectional"))
    )
    (net (code "62") (name "/SWCLK") (class "Default")
      (node (ref "P1") (pin "2") (pinfunction "2_2") (pintype "passive"))
      (node (ref "U1") (pin "76") (pinfunction "PA14(JTCK-SWCLK)_76") (pintype "bidirectional"))
    )
    (net (code "63") (name "/SWDIO") (class "Default")
      (node (ref "P1") (pin "1") (pinfunction "1_1") (pintype "passive"))
      (node (ref "U1") (pin "72") (pinfunction "PA13(JTMS-SWDIO)_72") (pintype "bidirectional"))
    )
    (net (code "64") (name "/SWO") (class "Default")
      (node (ref "P1") (pin "3") (pinfunction "3_3") (pintype "passive"))
      (node (ref "U1") (pin "89") (pinfunction "PB3(JTDO/TRACESWO)_89") (pintype "bidirectional"))
    )
    (net (code "65") (name "/TOF_INT_1") (class "Default")
      (node (ref "J2") (pin "1") (pinfunction "1_1") (pintype "passive"))
      (node (ref "U1") (pin "44") (pinfunction "PE13_44") (pintype "bidirectional"))
    )
    (net (code "66") (name "/TOF_INT_2") (class "Default")
      (node (ref "J3") (pin "1") (pinfunction "1_1") (pintype "passive"))
      (node (ref "U1") (pin "68") (pinfunction "PA9_68") (pintype "bidirectional"))
    )
    (net (code "67") (name "/TOF_INT_3") (class "Default")
      (node (ref "J5") (pin "1") (pinfunction "1_1") (pintype "passive"))
      (node (ref "U1") (pin "62") (pinfunction "PD15_62") (pintype "bidirectional"))
    )
    (net (code "68") (name "/TOF_INT_4") (class "Default")
      (node (ref "J8") (pin "1") (pinfunction "1_1") (pintype "passive"))
      (node (ref "U1") (pin "59") (pinfunction "PD12_59") (pintype "bidirectional"))
    )
    (net (code "69") (name "/TOF_INT_5") (class "Default")
      (node (ref "J14") (pin "1") (pinfunction "1_1") (pintype "passive"))
      (node (ref "U1") (pin "57") (pinfunction "PD10_57") (pintype "bidirectional"))
    )
    (net (code "70") (name "/TOF_INT_6") (class "Default")
      (node (ref "J15") (pin "1") (pinfunction "1_1") (pintype "passive"))
      (node (ref "U1") (pin "46") (pinfunction "PE15_46") (pintype "bidirectional"))
    )
    (net (code "71") (name "/TOF_LPIN_1") (class "Default")
      (node (ref "J2") (pin "2") (pinfunction "2_2") (pintype "passive"))
      (node (ref "U1") (pin "43") (pinfunction "PE12_43") (pintype "bidirectional"))
    )
    (net (code "72") (name "/TOF_LPIN_2") (class "Default")
      (node (ref "J3") (pin "2") (pinfunction "2_2") (pintype "passive"))
      (node (ref "U1") (pin "67") (pinfunction "PA8_67") (pintype "bidirectional"))
    )
    (net (code "73") (name "/TOF_LPIN_3") (class "Default")
      (node (ref "J5") (pin "2") (pinfunction "2_2") (pintype "passive"))
      (node (ref "U1") (pin "61") (pinfunction "PD14_61") (pintype "bidirectional"))
    )
    (net (code "74") (name "/TOF_LPIN_4") (class "Default")
      (node (ref "J8") (pin "2") (pinfunction "2_2") (pintype "passive"))
      (node (ref "U1") (pin "58") (pinfunction "PD11_58") (pintype "bidirectional"))
    )
    (net (code "75") (name "/TOF_LPIN_5") (class "Default")
      (node (ref "J14") (pin "2") (pinfunction "2_2") (pintype "passive"))
      (node (ref "U1") (pin "56") (pinfunction "PD9_56") (pintype "bidirectional"))
    )
    (net (code "76") (name "/TOF_LPIN_6") (class "Default")
      (node (ref "J15") (pin "2") (pinfunction "2_2") (pintype "passive"))
      (node (ref "U1") (pin "45") (pinfunction "PE14_45") (pintype "bidirectional"))
    )
    (net (code "77") (name "GND") (class "Default")
      (node (ref "C11") (pin "1") (pinfunction "1_1") (pintype "passive"))
      (node (ref "C12") (pin "2") (pinfunction "2_2") (pintype "passive"))
      (node (ref "C13") (pin "2") (pinfunction "2_2") (pintype "passive"))
      (node (ref "C20") (pin "2") (pinfunction "2_2") (pintype "passive"))
      (node (ref "C21") (pin "2") (pinfunction "2_2") (pintype "passive"))
      (node (ref "C22") (pin "2") (pinfunction "2_2") (pintype "passive"))
      (node (ref "C37") (pin "2") (pinfunction "2_2") (pintype "passive"))
      (node (ref "C38") (pin "2") (pinfunction "2_2") (pintype "passive"))
      (node (ref "C39") (pin "2") (pinfunction "2_2") (pintype "passive"))
      (node (ref "C40") (pin "2") (pinfunction "2_2") (pintype "passive"))
      (node (ref "C41") (pin "2") (pinfunction "2_2") (pintype "passive"))
      (node (ref "C42") (pin "2") (pinfunction "2_2") (pintype "passive"))
      (node (ref "C43") (pin "1") (pinfunction "1_1") (pintype "passive"))
      (node (ref "C44") (pin "2") (pinfunction "2_2") (pintype "passive"))
      (node (ref "C45") (pin "2") (pinfunction "2_2") (pintype "passive"))
      (node (ref "C46") (pin "2") (pinfunction "2_2") (pintype "passive"))
      (node (ref "C47") (pin "2") (pinfunction "2_2") (pintype "passive"))
      (node (ref "C48") (pin "2") (pinfunction "2_2") (pintype "passive"))
      (node (ref "J1") (pin "7") (pinfunction "7_7") (pintype "passive"))
      (node (ref "J10") (pin "1") (pinfunction "1_1") (pintype "passive"))
      (node (ref "J11") (pin "5") (pinfunction "5_5") (pintype "passive"))
      (node (ref "J12") (pin "1") (pinfunction "1_1") (pintype "passive"))
      (node (ref "J13") (pin "1") (pinfunction "1_1") (pintype "passive"))
      (node (ref "J14") (pin "5") (pinfunction "5_5") (pintype "passive"))
      (node (ref "J15") (pin "5") (pinfunction "5_5") (pintype "passive"))
      (node (ref "J16") (pin "5") (pinfunction "5_5") (pintype "passive"))
      (node (ref "J17") (pin "5") (pinfunction "5_5") (pintype "passive"))
      (node (ref "J18") (pin "3") (pinfunction "3_3") (pintype "passive"))
      (node (ref "J2") (pin "5") (pinfunction "5_5") (pintype "passive"))
      (node (ref "J23") (pin "5") (pinfunction "5_5") (pintype "passive"))
      (node (ref "J3") (pin "5") (pinfunction "5_5") (pintype "passive"))
      (node (ref "J4") (pin "3") (pinfunction "3_3") (pintype "passive"))
      (node (ref "J5") (pin "5") (pinfunction "5_5") (pintype "passive"))
      (node (ref "J6") (pin "1") (pinfunction "1_1") (pintype "passive"))
      (node (ref "J7") (pin "5") (pinfunction "5_5") (pintype "passive"))
      (node (ref "J8") (pin "5") (pinfunction "5_5") (pintype "passive"))
      (node (ref "J9") (pin "1") (pinfunction "1_1") (pintype "passive"))
      (node (ref "P1") (pin "5") (pinfunction "5_5") (pintype "passive"))
      (node (ref "P2") (pin "2") (pinfunction "2_2") (pintype "passive"))
      (node (ref "R18") (pin "1") (pinfunction "1_1") (pintype "passive"))
      (node (ref "U1") (pin "10") (pinfunction "VSS_10") (pintype "power_in"))
      (node (ref "U1") (pin "20") (pinfunction "VSSA_20") (pintype "power_in"))
      (node (ref "U1") (pin "27") (pinfunction "VSS_27") (pintype "power_in"))
      (node (ref "U1") (pin "74") (pinfunction "VSS_74") (pintype "power_in"))
      (node (ref "U1") (pin "99") (pinfunction "VSS_99") (pintype "power_in"))
      (node (ref "U4") (pin "1") (pinfunction "A0_1") (pintype "input"))
      (node (ref "U4") (pin "13") (pinfunction "A2_13") (pintype "input"))
      (node (ref "U4") (pin "2") (pinfunction "A1_2") (pintype "input"))
      (node (ref "U4") (pin "8") (pinfunction "GND_8") (pintype "power_in"))
      (node (ref "Y1") (pin "2") (pinfunction "NO_CONNECT_1_2") (pintype "passive"))
      (node (ref "Y1") (pin "4") (pinfunction "NO_CONNECT_2_4") (pintype "passive"))
    )
    (net (code "78") (name "Net-(J4-Pad2)") (class "Default")
      (node (ref "J4") (pin "2") (pinfunction "2_2") (pintype "passive"))
      (node (ref "R17") (pin "2") (pinfunction "2_2") (pintype "passive"))
    )
    (net (code "79") (name "Net-(J18-Pad2)") (class "Default")
      (node (ref "J18") (pin "2") (pinfunction "2_2") (pintype "passive"))
      (node (ref "R27") (pin "1") (pinfunction "1_1") (pintype "passive"))
    )
    (net (code "80") (name "Net-(U1A-BOOT0)") (class "Default")
      (node (ref "R27") (pin "2") (pinfunction "2_2") (pintype "passive"))
      (node (ref "U1") (pin "94") (pinfunction "BOOT0_94") (pintype "input"))
    )
    (net (code "81") (name "Net-(U1A-NRST)") (class "Default")
      (node (ref "C48") (pin "1") (pinfunction "1_1") (pintype "passive"))
      (node (ref "R26") (pin "2") (pinfunction "2_2") (pintype "passive"))
      (node (ref "U1") (pin "14") (pinfunction "NRST_14") (pintype "bidirectional"))
    )
    (net (code "82") (name "Net-(U1A-VCAP_1)") (class "Default")
      (node (ref "C21") (pin "1") (pinfunction "1_1") (pintype "passive"))
      (node (ref "U1") (pin "49") (pinfunction "VCAP_1_49") (pintype "power_in"))
    )
    (net (code "83") (name "Net-(U1A-VCAP_2)") (class "Default")
      (node (ref "C20") (pin "1") (pinfunction "1_1") (pintype "passive"))
      (node (ref "U1") (pin "73") (pinfunction "VCAP_2_73") (pintype "power_in"))
    )
    (net (code "84") (name "Net-(U4-SC0)") (class "Default")
      (node (ref "J7") (pin "3") (pinfunction "3_3") (pintype "passive"))
      (node (ref "U4") (pin "5") (pinfunction "SC0_5") (pintype "bidirectional"))
    )
    (net (code "85") (name "Net-(U4-SC1)") (class "Default")
      (node (ref "J11") (pin "3") (pinfunction "3_3") (pintype "passive"))
      (node (ref "U4") (pin "7") (pinfunction "SC1_7") (pintype "bidirectional"))
    )
    (net (code "86") (name "Net-(U4-SC2)") (class "Default")
      (node (ref "J16") (pin "3") (pinfunction "3_3") (pintype "passive"))
      (node (ref "U4") (pin "10") (pinfunction "SC2_10") (pintype "bidirectional"))
    )
    (net (code "87") (name "Net-(U4-SC3)") (class "Default")
      (node (ref "J17") (pin "3") (pinfunction "3_3") (pintype "passive"))
      (node (ref "U4") (pin "12") (pinfunction "SC3_12") (pintype "bidirectional"))
    )
    (net (code "88") (name "Net-(U4-SD0)") (class "Default")
      (node (ref "J7") (pin "4") (pinfunction "4_4") (pintype "passive"))
      (node (ref "U4") (pin "4") (pinfunction "SD0_4") (pintype "bidirectional"))
    )
    (net (code "89") (name "Net-(U4-SD1)") (class "Default")
      (node (ref "J11") (pin "4") (pinfunction "4_4") (pintype "passive"))
      (node (ref "U4") (pin "6") (pinfunction "SD1_6") (pintype "bidirectional"))
    )
    (net (code "90") (name "Net-(U4-SD2)") (class "Default")
      (node (ref "J16") (pin "4") (pinfunction "4_4") (pintype "passive"))
      (node (ref "U4") (pin "9") (pinfunction "SD2_9") (pintype "bidirectional"))
    )
    (net (code "91") (name "Net-(U4-SD3)") (class "Default")
      (node (ref "J17") (pin "4") (pinfunction "4_4") (pintype "passive"))
      (node (ref "U4") (pin "11") (pinfunction "SD3_11") (pintype "bidirectional"))
    )
    (net (code "92") (name "Net-(U4-~{RESET})") (class "Default")
      (node (ref "R20") (pin "1") (pinfunction "1_1") (pintype "passive"))
      (node (ref "U4") (pin "3") (pinfunction "~{RESET}_3") (pintype "input"))
    )
    (net (code "93") (name "Net-(Y1-CRYSTAL_TERMINAL_2)") (class "Default")
      (node (ref "C45") (pin "1") (pinfunction "1_1") (pintype "passive"))
      (node (ref "R19") (pin "1") (pinfunction "1_1") (pintype "passive"))
      (node (ref "Y1") (pin "3") (pinfunction "CRYSTAL_TERMINAL_2_3") (pintype "passive"))
    )
    (net (code "94") (name "unconnected-(J1-MNT_1-Pad9)") (class "Default")
      (node (ref "J1") (pin "9") (pinfunction "MNT_1_9") (pintype "passive"))
    )
    (net (code "95") (name "unconnected-(J1-MNT_2-Pad10)") (class "Default")
      (node (ref "J1") (pin "10") (pinfunction "MNT_2_10") (pintype "passive"))
    )
    (net (code "96") (name "unconnected-(J2-PadMP1)") (class "Default")
      (node (ref "J2") (pin "MP1") (pinfunction "MP1_MP1") (pintype "passive"))
    )
    (net (code "97") (name "unconnected-(J2-PadMP2)") (class "Default")
      (node (ref "J2") (pin "MP2") (pinfunction "MP2_MP2") (pintype "passive"))
    )
    (net (code "98") (name "unconnected-(J3-PadMP1)") (class "Default")
      (node (ref "J3") (pin "MP1") (pinfunction "MP1_MP1") (pintype "passive"))
    )
    (net (code "99") (name "unconnected-(J3-PadMP2)") (class "Default")
      (node (ref "J3") (pin "MP2") (pinfunction "MP2_MP2") (pintype "passive"))
    )
    (net (code "100") (name "unconnected-(J5-PadMP1)") (class "Default")
      (node (ref "J5") (pin "MP1") (pinfunction "MP1_MP1") (pintype "passive"))
    )
    (net (code "101") (name "unconnected-(J5-PadMP2)") (class "Default")
      (node (ref "J5") (pin "MP2") (pinfunction "MP2_MP2") (pintype "passive"))
    )
    (net (code "102") (name "unconnected-(J7-PadMP1)") (class "Default")
      (node (ref "J7") (pin "MP1") (pinfunction "MP1_MP1") (pintype "passive"))
    )
    (net (code "103") (name "unconnected-(J7-PadMP2)") (class "Default")
      (node (ref "J7") (pin "MP2") (pinfunction "MP2_MP2") (pintype "passive"))
    )
    (net (code "104") (name "unconnected-(J8-PadMP1)") (class "Default")
      (node (ref "J8") (pin "MP1") (pinfunction "MP1_MP1") (pintype "passive"))
    )
    (net (code "105") (name "unconnected-(J8-PadMP2)") (class "Default")
      (node (ref "J8") (pin "MP2") (pinfunction "MP2_MP2") (pintype "passive"))
    )
    (net (code "106") (name "unconnected-(J11-PadMP1)") (class "Default")
      (node (ref "J11") (pin "MP1") (pinfunction "MP1_MP1") (pintype "passive"))
    )
    (net (code "107") (name "unconnected-(J11-PadMP2)") (class "Default")
      (node (ref "J11") (pin "MP2") (pinfunction "MP2_MP2") (pintype "passive"))
    )
    (net (code "108") (name "unconnected-(J14-PadMP1)") (class "Default")
      (node (ref "J14") (pin "MP1") (pinfunction "MP1_MP1") (pintype "passive"))
    )
    (net (code "109") (name "unconnected-(J14-PadMP2)") (class "Default")
      (node (ref "J14") (pin "MP2") (pinfunction "MP2_MP2") (pintype "passive"))
    )
    (net (code "110") (name "unconnected-(J15-PadMP1)") (class "Default")
      (node (ref "J15") (pin "MP1") (pinfunction "MP1_MP1") (pintype "passive"))
    )
    (net (code "111") (name "unconnected-(J15-PadMP2)") (class "Default")
      (node (ref "J15") (pin "MP2") (pinfunction "MP2_MP2") (pintype "passive"))
    )
    (net (code "112") (name "unconnected-(J16-PadMP1)") (class "Default")
      (node (ref "J16") (pin "MP1") (pinfunction "MP1_MP1") (pintype "passive"))
    )
    (net (code "113") (name "unconnected-(J16-PadMP2)") (class "Default")
      (node (ref "J16") (pin "MP2") (pinfunction "MP2_MP2") (pintype "passive"))
    )
    (net (code "114") (name "unconnected-(J17-PadMP1)") (class "Default")
      (node (ref "J17") (pin "MP1") (pinfunction "MP1_MP1") (pintype "passive"))
    )
    (net (code "115") (name "unconnected-(J17-PadMP2)") (class "Default")
      (node (ref "J17") (pin "MP2") (pinfunction "MP2_MP2") (pintype "passive"))
    )
    (net (code "116") (name "unconnected-(J23-Pad1)") (class "Default")
      (node (ref "J23") (pin "1") (pinfunction "1_1") (pintype "passive"))
    )
    (net (code "117") (name "unconnected-(J23-Pad2)") (class "Default")
      (node (ref "J23") (pin "2") (pinfunction "2_2") (pintype "passive"))
    )
    (net (code "118") (name "unconnected-(J23-PadMP1)") (class "Default")
      (node (ref "J23") (pin "MP1") (pinfunction "MP1_MP1") (pintype "passive"))
    )
    (net (code "119") (name "unconnected-(J23-PadMP2)") (class "Default")
      (node (ref "J23") (pin "MP2") (pinfunction "MP2_MP2") (pintype "passive"))
    )
    (net (code "120") (name "unconnected-(U1A-PA4-Pad29)") (class "Default")
      (node (ref "U1") (pin "29") (pinfunction "PA4_29") (pintype "bidirectional"))
    )
    (net (code "121") (name "unconnected-(U1A-PA10-Pad69)") (class "Default")
      (node (ref "U1") (pin "69") (pinfunction "PA10_69") (pintype "bidirectional"))
    )
    (net (code "122") (name "unconnected-(U1A-PB9-Pad96)") (class "Default")
      (node (ref "U1") (pin "96") (pinfunction "PB9_96") (pintype "bidirectional"))
    )
    (net (code "123") (name "unconnected-(U1A-PC3-Pad18)") (class "Default")
      (node (ref "U1") (pin "18") (pinfunction "PC3_18") (pintype "bidirectional"))
    )
    (net (code "124") (name "unconnected-(U1A-PC13-Pad7)") (class "Default")
      (node (ref "U1") (pin "7") (pinfunction "PC13_7") (pintype "bidirectional"))
    )
    (net (code "125") (name "unconnected-(U1A-PC14-OSC32_IN(PC14)-Pad8)") (class "Default")
      (node (ref "U1") (pin "8") (pinfunction "PC14-OSC32_IN(PC14)_8") (pintype "bidirectional"))
    )
    (net (code "126") (name "unconnected-(U1A-PC15-OSC32_OUT(PC15)-Pad9)") (class "Default")
      (node (ref "U1") (pin "9") (pinfunction "PC15-OSC32_OUT(PC15)_9") (pintype "bidirectional"))
    )
    (net (code "127") (name "unconnected-(U1A-PD8-Pad55)") (class "Default")
      (node (ref "U1") (pin "55") (pinfunction "PD8_55") (pintype "bidirectional"))
    )
    (net (code "128") (name "unconnected-(U1A-PE10-Pad41)") (class "Default")
      (node (ref "U1") (pin "41") (pinfunction "PE10_41") (pintype "bidirectional"))
    )
  )
)
